# Bus_isolator_trager.net
KiCad netlist of a schematic drawn in EAGLE
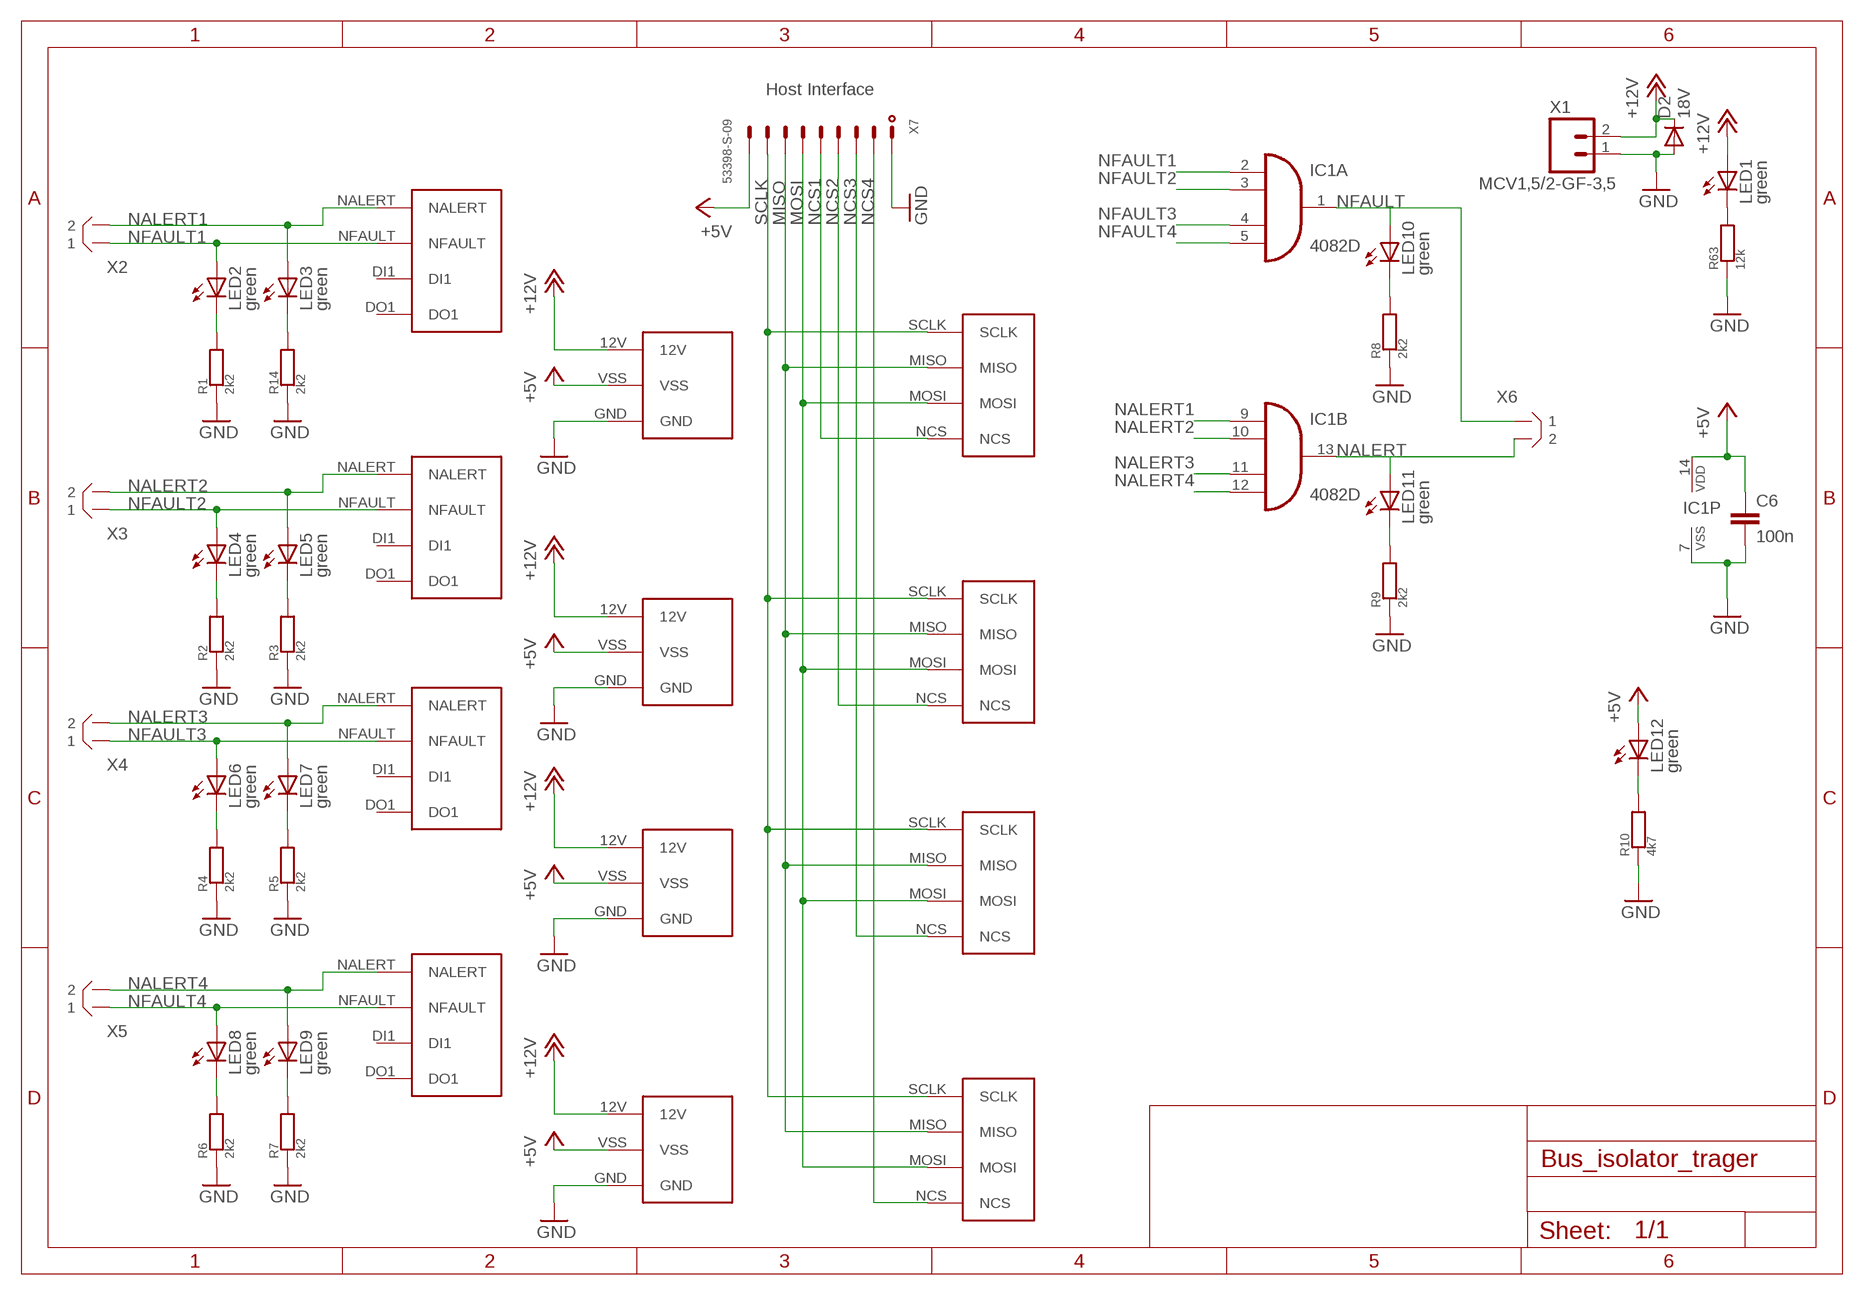
[diagram p0: schematic, sheet 1]

(export (version "E")
  (design (tool "Eeschema 10.0.6"))
  (components
    (comp (ref "A1")
      (value "SPI_ISOLATOR_V4")
      (footprint "eagle-import:SPI_ISOLATOR_V4")
      (libsource (lib "eagle-import") (part "SPI_ISOLATOR_V4"))
    )
    (comp (ref "A2")
      (value "SPI_ISOLATOR_V4")
      (footprint "eagle-import:SPI_ISOLATOR_V4")
      (libsource (lib "eagle-import") (part "SPI_ISOLATOR_V4"))
    )
    (comp (ref "A3")
      (value "SPI_ISOLATOR_V4")
      (footprint "eagle-import:SPI_ISOLATOR_V4")
      (libsource (lib "eagle-import") (part "SPI_ISOLATOR_V4"))
    )
    (comp (ref "A4")
      (value "SPI_ISOLATOR_V4")
      (footprint "eagle-import:SPI_ISOLATOR_V4")
      (libsource (lib "eagle-import") (part "SPI_ISOLATOR_V4"))
    )
    (comp (ref "C6")
      (value "100n")
      (footprint "eagle-import:C0603")
      (libsource (lib "eagle-import") (part "C-EUC0603"))
    )
    (comp (ref "D2")
      (value "18V")
      (footprint "eagle-import:DO214AA")
      (libsource (lib "eagle-import") (part "DIODE-DO214AA"))
    )
    (comp (ref "IC1")
      (value "4082D")
      (footprint "eagle-import:SO14")
      (libsource (lib "eagle-import") (part "4082D"))
    )
    (comp (ref "LED1")
      (value "green")
      (footprint "eagle-import:CHIP-LED0805")
      (libsource (lib "eagle-import") (part "LEDCHIP-LED0805"))
    )
    (comp (ref "LED2")
      (value "green")
      (footprint "eagle-import:CHIPLED_0805")
      (libsource (lib "eagle-import") (part "LEDCHIPLED_0805"))
    )
    (comp (ref "LED3")
      (value "green")
      (footprint "eagle-import:CHIPLED_0805")
      (libsource (lib "eagle-import") (part "LEDCHIPLED_0805"))
    )
    (comp (ref "LED4")
      (value "green")
      (footprint "eagle-import:CHIPLED_0805")
      (libsource (lib "eagle-import") (part "LEDCHIPLED_0805"))
    )
    (comp (ref "LED5")
      (value "green")
      (footprint "eagle-import:CHIPLED_0805")
      (libsource (lib "eagle-import") (part "LEDCHIPLED_0805"))
    )
    (comp (ref "LED6")
      (value "green")
      (footprint "eagle-import:CHIPLED_0805")
      (libsource (lib "eagle-import") (part "LEDCHIPLED_0805"))
    )
    (comp (ref "LED7")
      (value "green")
      (footprint "eagle-import:CHIPLED_0805")
      (libsource (lib "eagle-import") (part "LEDCHIPLED_0805"))
    )
    (comp (ref "LED8")
      (value "green")
      (footprint "eagle-import:CHIPLED_0805")
      (libsource (lib "eagle-import") (part "LEDCHIPLED_0805"))
    )
    (comp (ref "LED9")
      (value "green")
      (footprint "eagle-import:CHIPLED_0805")
      (libsource (lib "eagle-import") (part "LEDCHIPLED_0805"))
    )
    (comp (ref "LED10")
      (value "green")
      (footprint "eagle-import:CHIPLED_0805")
      (libsource (lib "eagle-import") (part "LEDCHIPLED_0805"))
    )
    (comp (ref "LED11")
      (value "green")
      (footprint "eagle-import:CHIPLED_0805")
      (libsource (lib "eagle-import") (part "LEDCHIPLED_0805"))
    )
    (comp (ref "LED12")
      (value "green")
      (footprint "eagle-import:CHIP-LED0805")
      (libsource (lib "eagle-import") (part "LEDCHIP-LED0805"))
    )
    (comp (ref "R1")
      (value "2k2")
      (footprint "eagle-import:R0603")
      (libsource (lib "eagle-import") (part "R0603"))
    )
    (comp (ref "R2")
      (value "2k2")
      (footprint "eagle-import:R0603")
      (libsource (lib "eagle-import") (part "R0603"))
    )
    (comp (ref "R3")
      (value "2k2")
      (footprint "eagle-import:R0603")
      (libsource (lib "eagle-import") (part "R0603"))
    )
    (comp (ref "R4")
      (value "2k2")
      (footprint "eagle-import:R0603")
      (libsource (lib "eagle-import") (part "R0603"))
    )
    (comp (ref "R5")
      (value "2k2")
      (footprint "eagle-import:R0603")
      (libsource (lib "eagle-import") (part "R0603"))
    )
    (comp (ref "R6")
      (value "2k2")
      (footprint "eagle-import:R0603")
      (libsource (lib "eagle-import") (part "R0603"))
    )
    (comp (ref "R7")
      (value "2k2")
      (footprint "eagle-import:R0603")
      (libsource (lib "eagle-import") (part "R0603"))
    )
    (comp (ref "R8")
      (value "2k2")
      (footprint "eagle-import:R0603")
      (libsource (lib "eagle-import") (part "R0603"))
    )
    (comp (ref "R9")
      (value "2k2")
      (footprint "eagle-import:R0603")
      (libsource (lib "eagle-import") (part "R0603"))
    )
    (comp (ref "R10")
      (value "4k7")
      (footprint "eagle-import:R0603")
      (libsource (lib "eagle-import") (part "R0603"))
    )
    (comp (ref "R14")
      (value "2k2")
      (footprint "eagle-import:R0603")
      (libsource (lib "eagle-import") (part "R0603"))
    )
    (comp (ref "R63")
      (value "12k")
      (footprint "eagle-import:R0603")
      (libsource (lib "eagle-import") (part "R0603"))
    )
    (comp (ref "X1")
      (value "MCV1,5/2-GF-3,5")
      (footprint "eagle-import:MCV1,5_2-GF-3,5")
      (libsource (lib "eagle-import") (part "MCV1,5/2-GF-3,5"))
    )
    (comp (ref "X2")
      (value "B2B-XH")
      (footprint "eagle-import:B2B-XH")
      (libsource (lib "eagle-import") (part "?2B-XHB"))
    )
    (comp (ref "X3")
      (value "B2B-XH")
      (footprint "eagle-import:B2B-XH")
      (libsource (lib "eagle-import") (part "?2B-XHB"))
    )
    (comp (ref "X4")
      (value "B2B-XH")
      (footprint "eagle-import:B2B-XH")
      (libsource (lib "eagle-import") (part "?2B-XHB"))
    )
    (comp (ref "X5")
      (value "B2B-XH")
      (footprint "eagle-import:B2B-XH")
      (libsource (lib "eagle-import") (part "?2B-XHB"))
    )
    (comp (ref "X6")
      (value "B2B-XH")
      (footprint "eagle-import:B2B-XH")
      (libsource (lib "eagle-import") (part "?2B-XHB"))
    )
    (comp (ref "X7")
      (value "53398-S-09")
      (footprint "eagle-import:53398-09-S")
      (libsource (lib "eagle-import") (part "53?-09398-S"))
    )
  )
  (nets
    (net (code "1") (name "+5V") (class "Default")
      (node (ref "A1") (pin "VSS") (pinfunction "VSS_VSS") (pintype "bidirectional"))
      (node (ref "A2") (pin "VSS") (pinfunction "VSS_VSS") (pintype "bidirectional"))
      (node (ref "A3") (pin "VSS") (pinfunction "VSS_VSS") (pintype "bidirectional"))
      (node (ref "A4") (pin "VSS") (pinfunction "VSS_VSS") (pintype "bidirectional"))
      (node (ref "C6") (pin "1") (pinfunction "1_1") (pintype "passive"))
      (node (ref "IC1") (pin "14") (pinfunction "VDD_14") (pintype "power_in"))
      (node (ref "LED12") (pin "A") (pinfunction "A_A") (pintype "passive"))
      (node (ref "X7") (pin "9") (pinfunction "9_9") (pintype "passive"))
    )
    (net (code "2") (name "+12V") (class "Default")
      (node (ref "A1") (pin "12V") (pinfunction "12V_12V") (pintype "bidirectional"))
      (node (ref "A2") (pin "12V") (pinfunction "12V_12V") (pintype "bidirectional"))
      (node (ref "A3") (pin "12V") (pinfunction "12V_12V") (pintype "bidirectional"))
      (node (ref "A4") (pin "12V") (pinfunction "12V_12V") (pintype "bidirectional"))
      (node (ref "D2") (pin "C") (pinfunction "C_C") (pintype "passive"))
      (node (ref "LED1") (pin "A") (pinfunction "A_A") (pintype "passive"))
      (node (ref "X1") (pin "2") (pinfunction "2_2") (pintype "passive"))
    )
    (net (code "3") (name "/MISO") (class "Default")
      (node (ref "A1") (pin "MISO") (pinfunction "MISO_MISO") (pintype "bidirectional"))
      (node (ref "A2") (pin "MISO") (pinfunction "MISO_MISO") (pintype "bidirectional"))
      (node (ref "A3") (pin "MISO") (pinfunction "MISO_MISO") (pintype "bidirectional"))
      (node (ref "A4") (pin "MISO") (pinfunction "MISO_MISO") (pintype "bidirectional"))
      (node (ref "X7") (pin "7") (pinfunction "7_7") (pintype "passive"))
    )
    (net (code "4") (name "/MOSI") (class "Default")
      (node (ref "A1") (pin "MOSI") (pinfunction "MOSI_MOSI") (pintype "bidirectional"))
      (node (ref "A2") (pin "MOSI") (pinfunction "MOSI_MOSI") (pintype "bidirectional"))
      (node (ref "A3") (pin "MOSI") (pinfunction "MOSI_MOSI") (pintype "bidirectional"))
      (node (ref "A4") (pin "MOSI") (pinfunction "MOSI_MOSI") (pintype "bidirectional"))
      (node (ref "X7") (pin "6") (pinfunction "6_6") (pintype "passive"))
    )
    (net (code "5") (name "/NALERT") (class "Default")
      (node (ref "IC1") (pin "13") (pinfunction "O_13") (pintype "output"))
      (node (ref "LED11") (pin "A") (pinfunction "A_A") (pintype "passive"))
      (node (ref "X6") (pin "P$2") (pinfunction "2_P$2") (pintype "bidirectional"))
    )
    (net (code "6") (name "/NALERT1") (class "Default")
      (node (ref "A1") (pin "NALERT") (pinfunction "NALERT_NALERT") (pintype "bidirectional"))
      (node (ref "IC1") (pin "9") (pinfunction "I0_9") (pintype "input"))
      (node (ref "LED3") (pin "A") (pinfunction "A_A") (pintype "passive"))
      (node (ref "X2") (pin "P$2") (pinfunction "2_P$2") (pintype "bidirectional"))
    )
    (net (code "7") (name "/NALERT2") (class "Default")
      (node (ref "A2") (pin "NALERT") (pinfunction "NALERT_NALERT") (pintype "bidirectional"))
      (node (ref "IC1") (pin "10") (pinfunction "I1_10") (pintype "input"))
      (node (ref "LED5") (pin "A") (pinfunction "A_A") (pintype "passive"))
      (node (ref "X3") (pin "P$2") (pinfunction "2_P$2") (pintype "bidirectional"))
    )
    (net (code "8") (name "/NALERT3") (class "Default")
      (node (ref "A3") (pin "NALERT") (pinfunction "NALERT_NALERT") (pintype "bidirectional"))
      (node (ref "IC1") (pin "11") (pinfunction "I2_11") (pintype "input"))
      (node (ref "LED7") (pin "A") (pinfunction "A_A") (pintype "passive"))
      (node (ref "X4") (pin "P$2") (pinfunction "2_P$2") (pintype "bidirectional"))
    )
    (net (code "9") (name "/NALERT4") (class "Default")
      (node (ref "A4") (pin "NALERT") (pinfunction "NALERT_NALERT") (pintype "bidirectional"))
      (node (ref "IC1") (pin "12") (pinfunction "I3_12") (pintype "input"))
      (node (ref "LED9") (pin "A") (pinfunction "A_A") (pintype "passive"))
      (node (ref "X5") (pin "P$2") (pinfunction "2_P$2") (pintype "bidirectional"))
    )
    (net (code "10") (name "/NCS1") (class "Default")
      (node (ref "A1") (pin "NCS") (pinfunction "NCS_NCS") (pintype "bidirectional"))
      (node (ref "X7") (pin "5") (pinfunction "5_5") (pintype "passive"))
    )
    (net (code "11") (name "/NCS2") (class "Default")
      (node (ref "A2") (pin "NCS") (pinfunction "NCS_NCS") (pintype "bidirectional"))
      (node (ref "X7") (pin "4") (pinfunction "4_4") (pintype "passive"))
    )
    (net (code "12") (name "/NCS3") (class "Default")
      (node (ref "A3") (pin "NCS") (pinfunction "NCS_NCS") (pintype "bidirectional"))
      (node (ref "X7") (pin "3") (pinfunction "3_3") (pintype "passive"))
    )
    (net (code "13") (name "/NCS4") (class "Default")
      (node (ref "A4") (pin "NCS") (pinfunction "NCS_NCS") (pintype "bidirectional"))
      (node (ref "X7") (pin "2") (pinfunction "2_2") (pintype "passive"))
    )
    (net (code "14") (name "/NFAULT") (class "Default")
      (node (ref "IC1") (pin "1") (pinfunction "O_1") (pintype "output"))
      (node (ref "LED10") (pin "A") (pinfunction "A_A") (pintype "passive"))
      (node (ref "X6") (pin "P$1") (pinfunction "1_P$1") (pintype "bidirectional"))
    )
    (net (code "15") (name "/NFAULT1") (class "Default")
      (node (ref "A1") (pin "NFAULT") (pinfunction "NFAULT_NFAULT") (pintype "bidirectional"))
      (node (ref "IC1") (pin "2") (pinfunction "I0_2") (pintype "input"))
      (node (ref "LED2") (pin "A") (pinfunction "A_A") (pintype "passive"))
      (node (ref "X2") (pin "P$1") (pinfunction "1_P$1") (pintype "bidirectional"))
    )
    (net (code "16") (name "/NFAULT2") (class "Default")
      (node (ref "A2") (pin "NFAULT") (pinfunction "NFAULT_NFAULT") (pintype "bidirectional"))
      (node (ref "IC1") (pin "3") (pinfunction "I1_3") (pintype "input"))
      (node (ref "LED4") (pin "A") (pinfunction "A_A") (pintype "passive"))
      (node (ref "X3") (pin "P$1") (pinfunction "1_P$1") (pintype "bidirectional"))
    )
    (net (code "17") (name "/NFAULT3") (class "Default")
      (node (ref "A3") (pin "NFAULT") (pinfunction "NFAULT_NFAULT") (pintype "bidirectional"))
      (node (ref "IC1") (pin "4") (pinfunction "I2_4") (pintype "input"))
      (node (ref "LED6") (pin "A") (pinfunction "A_A") (pintype "passive"))
      (node (ref "X4") (pin "P$1") (pinfunction "1_P$1") (pintype "bidirectional"))
    )
    (net (code "18") (name "/NFAULT4") (class "Default")
      (node (ref "A4") (pin "NFAULT") (pinfunction "NFAULT_NFAULT") (pintype "bidirectional"))
      (node (ref "IC1") (pin "5") (pinfunction "I3_5") (pintype "input"))
      (node (ref "LED8") (pin "A") (pinfunction "A_A") (pintype "passive"))
      (node (ref "X5") (pin "P$1") (pinfunction "1_P$1") (pintype "bidirectional"))
    )
    (net (code "19") (name "/SCLK") (class "Default")
      (node (ref "A1") (pin "SCLK") (pinfunction "SCLK_SCLK") (pintype "bidirectional"))
      (node (ref "A2") (pin "SCLK") (pinfunction "SCLK_SCLK") (pintype "bidirectional"))
      (node (ref "A3") (pin "SCLK") (pinfunction "SCLK_SCLK") (pintype "bidirectional"))
      (node (ref "A4") (pin "SCLK") (pinfunction "SCLK_SCLK") (pintype "bidirectional"))
      (node (ref "X7") (pin "8") (pinfunction "8_8") (pintype "passive"))
    )
    (net (code "20") (name "GND") (class "Default")
      (node (ref "A1") (pin "GND") (pinfunction "GND_GND") (pintype "bidirectional"))
      (node (ref "A2") (pin "GND") (pinfunction "GND_GND") (pintype "bidirectional"))
      (node (ref "A3") (pin "GND") (pinfunction "GND_GND") (pintype "bidirectional"))
      (node (ref "A4") (pin "GND") (pinfunction "GND_GND") (pintype "bidirectional"))
      (node (ref "C6") (pin "2") (pinfunction "2_2") (pintype "passive"))
      (node (ref "D2") (pin "A") (pinfunction "A_A") (pintype "passive"))
      (node (ref "IC1") (pin "7") (pinfunction "VSS_7") (pintype "power_in"))
      (node (ref "R1") (pin "1") (pinfunction "1_1") (pintype "passive"))
      (node (ref "R10") (pin "1") (pinfunction "1_1") (pintype "passive"))
      (node (ref "R14") (pin "1") (pinfunction "1_1") (pintype "passive"))
      (node (ref "R2") (pin "1") (pinfunction "1_1") (pintype "passive"))
      (node (ref "R3") (pin "1") (pinfunction "1_1") (pintype "passive"))
      (node (ref "R4") (pin "1") (pinfunction "1_1") (pintype "passive"))
      (node (ref "R5") (pin "1") (pinfunction "1_1") (pintype "passive"))
      (node (ref "R6") (pin "1") (pinfunction "1_1") (pintype "passive"))
      (node (ref "R63") (pin "1") (pinfunction "1_1") (pintype "passive"))
      (node (ref "R7") (pin "1") (pinfunction "1_1") (pintype "passive"))
      (node (ref "R8") (pin "1") (pinfunction "1_1") (pintype "passive"))
      (node (ref "R9") (pin "1") (pinfunction "1_1") (pintype "passive"))
      (node (ref "X1") (pin "1") (pinfunction "1_1") (pintype "passive"))
      (node (ref "X7") (pin "1") (pinfunction "1_1") (pintype "passive"))
    )
    (net (code "21") (name "Net-(LED1-PadC)") (class "Default")
      (node (ref "LED1") (pin "C") (pinfunction "C_C") (pintype "passive"))
      (node (ref "R63") (pin "2") (pinfunction "2_2") (pintype "passive"))
    )
    (net (code "22") (name "Net-(LED2-PadC)") (class "Default")
      (node (ref "LED2") (pin "C") (pinfunction "C_C") (pintype "passive"))
      (node (ref "R1") (pin "2") (pinfunction "2_2") (pintype "passive"))
    )
    (net (code "23") (name "Net-(LED3-PadC)") (class "Default")
      (node (ref "LED3") (pin "C") (pinfunction "C_C") (pintype "passive"))
      (node (ref "R14") (pin "2") (pinfunction "2_2") (pintype "passive"))
    )
    (net (code "24") (name "Net-(LED4-PadC)") (class "Default")
      (node (ref "LED4") (pin "C") (pinfunction "C_C") (pintype "passive"))
      (node (ref "R2") (pin "2") (pinfunction "2_2") (pintype "passive"))
    )
    (net (code "25") (name "Net-(LED5-PadC)") (class "Default")
      (node (ref "LED5") (pin "C") (pinfunction "C_C") (pintype "passive"))
      (node (ref "R3") (pin "2") (pinfunction "2_2") (pintype "passive"))
    )
    (net (code "26") (name "Net-(LED6-PadC)") (class "Default")
      (node (ref "LED6") (pin "C") (pinfunction "C_C") (pintype "passive"))
      (node (ref "R4") (pin "2") (pinfunction "2_2") (pintype "passive"))
    )
    (net (code "27") (name "Net-(LED7-PadC)") (class "Default")
      (node (ref "LED7") (pin "C") (pinfunction "C_C") (pintype "passive"))
      (node (ref "R5") (pin "2") (pinfunction "2_2") (pintype "passive"))
    )
    (net (code "28") (name "Net-(LED8-PadC)") (class "Default")
      (node (ref "LED8") (pin "C") (pinfunction "C_C") (pintype "passive"))
      (node (ref "R6") (pin "2") (pinfunction "2_2") (pintype "passive"))
    )
    (net (code "29") (name "Net-(LED9-PadC)") (class "Default")
      (node (ref "LED9") (pin "C") (pinfunction "C_C") (pintype "passive"))
      (node (ref "R7") (pin "2") (pinfunction "2_2") (pintype "passive"))
    )
    (net (code "30") (name "Net-(LED10-PadC)") (class "Default")
      (node (ref "LED10") (pin "C") (pinfunction "C_C") (pintype "passive"))
      (node (ref "R8") (pin "2") (pinfunction "2_2") (pintype "passive"))
    )
    (net (code "31") (name "Net-(LED11-PadC)") (class "Default")
      (node (ref "LED11") (pin "C") (pinfunction "C_C") (pintype "passive"))
      (node (ref "R9") (pin "2") (pinfunction "2_2") (pintype "passive"))
    )
    (net (code "32") (name "Net-(LED12-PadC)") (class "Default")
      (node (ref "LED12") (pin "C") (pinfunction "C_C") (pintype "passive"))
      (node (ref "R10") (pin "2") (pinfunction "2_2") (pintype "passive"))
    )
    (net (code "33") (name "unconnected-(A1-PadDI1)") (class "Default")
      (node (ref "A1") (pin "DI1") (pinfunction "DI1_DI1") (pintype "bidirectional"))
    )
    (net (code "34") (name "unconnected-(A1-PadDO1)") (class "Default")
      (node (ref "A1") (pin "DO1") (pinfunction "DO1_DO1") (pintype "bidirectional"))
    )
    (net (code "35") (name "unconnected-(A2-PadDI1)") (class "Default")
      (node (ref "A2") (pin "DI1") (pinfunction "DI1_DI1") (pintype "bidirectional"))
    )
    (net (code "36") (name "unconnected-(A2-PadDO1)") (class "Default")
      (node (ref "A2") (pin "DO1") (pinfunction "DO1_DO1") (pintype "bidirectional"))
    )
    (net (code "37") (name "unconnected-(A3-PadDI1)") (class "Default")
      (node (ref "A3") (pin "DI1") (pinfunction "DI1_DI1") (pintype "bidirectional"))
    )
    (net (code "38") (name "unconnected-(A3-PadDO1)") (class "Default")
      (node (ref "A3") (pin "DO1") (pinfunction "DO1_DO1") (pintype "bidirectional"))
    )
    (net (code "39") (name "unconnected-(A4-PadDI1)") (class "Default")
      (node (ref "A4") (pin "DI1") (pinfunction "DI1_DI1") (pintype "bidirectional"))
    )
    (net (code "40") (name "unconnected-(A4-PadDO1)") (class "Default")
      (node (ref "A4") (pin "DO1") (pinfunction "DO1_DO1") (pintype "bidirectional"))
    )
  )
)
